# USB_Type-C.net
KiCad netlist of a schematic drawn in Altium Designer
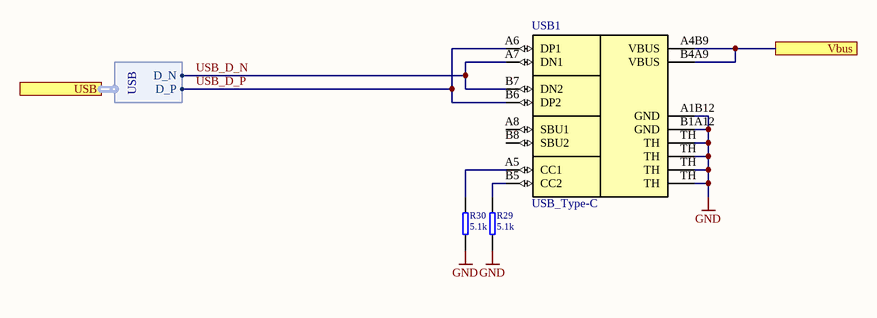
[diagram p0: USB_Type-C.SchDoc]

(export (version "E")
  (design (tool "Eeschema 10.0.6"))
  (components
    (comp (ref "R29")
      (value "5.1k")
      (footprint "RES 0402")
      (description "Resistor")
      (fields (field (name "Comment") "RES 0402 5.1k"))
      (libsource (lib "!main") (part "!Resistor"))
    )
    (comp (ref "R30")
      (value "5.1k")
      (footprint "RES 0402")
      (description "Resistor")
      (fields (field (name "Comment") "RES 0402 5.1k"))
      (libsource (lib "!main") (part "!Resistor"))
    )
    (comp (ref "USB1")
      (value "USB_Type-C")
      (footprint "USB_Type-C")
      (description "USB Type-C connector")
      (libsource (lib "connectors") (part "USB_Type-C"))
    )
  )
  (nets
    (net (code "2") (name "/USB_D_N") (class "Default")
      (node (ref "USB1") (pin "A7") (pinfunction "DN1_A7") (pintype "bidirectional"))
      (node (ref "USB1") (pin "B7") (pinfunction "DN2_B7") (pintype "bidirectional"))
    )
    (net (code "3") (name "/USB_D_P") (class "Default")
      (node (ref "USB1") (pin "A6") (pinfunction "DP1_A6") (pintype "bidirectional"))
      (node (ref "USB1") (pin "B6") (pinfunction "DP2_B6") (pintype "bidirectional"))
    )
    (net (code "4") (name "/Vbus") (class "Default")
      (node (ref "USB1") (pin "A4B9") (pinfunction "VBUS_A4B9") (pintype "power_in"))
      (node (ref "USB1") (pin "B4A9") (pinfunction "VBUS_B4A9") (pintype "power_in"))
    )
    (net (code "6") (name "GND") (class "Default")
      (node (ref "R29") (pin "1") (pinfunction "11_1") (pintype "passive"))
      (node (ref "R30") (pin "1") (pinfunction "11_1") (pintype "passive"))
      (node (ref "USB1") (pin "A1B12") (pinfunction "GND_A1B12") (pintype "power_in"))
      (node (ref "USB1") (pin "B1A12") (pinfunction "GND_B1A12") (pintype "power_in"))
      (node (ref "USB1") (pin "TH") (pinfunction "TH_TH") (pintype "passive"))
    )
    (net (code "7") (name "Net-(R29-12)") (class "Default")
      (node (ref "R29") (pin "2") (pinfunction "12_2") (pintype "passive"))
      (node (ref "USB1") (pin "B5") (pinfunction "CC2_B5") (pintype "bidirectional"))
    )
    (net (code "8") (name "Net-(R30-12)") (class "Default")
      (node (ref "R30") (pin "2") (pinfunction "12_2") (pintype "passive"))
      (node (ref "USB1") (pin "A5") (pinfunction "CC1_A5") (pintype "bidirectional"))
    )
    (net (code "9") (name "unconnected-(USB1-SBU1-PadA8)") (class "Default")
      (node (ref "USB1") (pin "A8") (pinfunction "SBU1_A8") (pintype "bidirectional"))
    )
    (net (code "10") (name "unconnected-(USB1-SBU2-PadB8)") (class "Default")
      (node (ref "USB1") (pin "B8") (pinfunction "SBU2_B8") (pintype "bidirectional"))
    )
  )
)
